# One_Digit_7_Seg_Display.net
KiCad netlist of a schematic drawn in Altium Designer
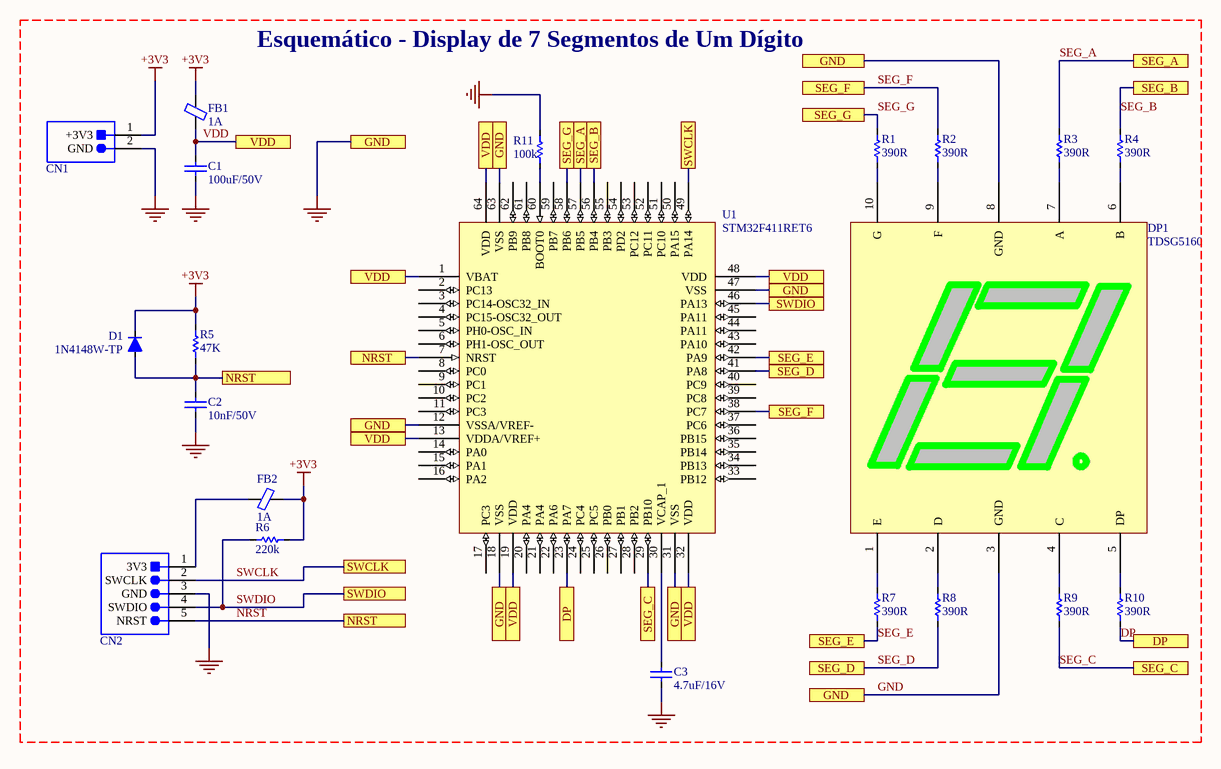
[diagram p0: One_Digit_7_Seg_Display.SchDoc]

(export (version "E")
  (design (tool "Eeschema 10.0.6"))
  (components
    (comp (ref "C1")
      (value "100uF/50V")
      (footprint "Capacitor 0805")
      (description "Cap Ceramic 0.1uF 50V X7R 20% SMD 0805 125C Paper T/R")
      (fields
        (field (name "MANUFACTURER") "Yageo")
        (field (name "MANUFACTURER PART NUMBER") "CC0805MRX7R9BB104")
      )
      (libsource (lib "Roniere_Lib") (part "CC0805MRX7R9BB104"))
    )
    (comp (ref "C2")
      (value "10nF/50V")
      (footprint "Capacitor 0805")
      (description "Cap Cer 0805 10NF 50V C0G 1%")
      (fields
        (field (name "MANUFACTURER") "KEMET")
        (field (name "MANUFACTURER PART NUMBER") "C0805X103F5GEC7210")
      )
      (libsource (lib "Roniere_Lib") (part "C0805X103F5GEC7210"))
    )
    (comp (ref "C3")
      (value "4.7uF/16V")
      (footprint "Capacitor 0805 4.7uF")
      (description "Multilayer Ceramic Capacitors MLCC - SMD/SMT 16volts 4.7uF X5R 20%")
      (fields
        (field (name "MANUFACTURER") "KEMET")
        (field (name "MANUFACTURER PART NUMBER") "C0805C475M4PACTU")
      )
      (libsource (lib "Roniere_Lib") (part "C0805C475M4PACTU"))
    )
    (comp (ref "CN1")
      (value "PCMC2-02 - Alimentação +3V3")
      (footprint "Header Male Horizontal 2X1")
      (libsource (lib "Roniere_Lib") (part "PCMC2-02 - Alimentação +3V3"))
    )
    (comp (ref "CN2")
      (value "PCMC2-05 - Gravacao STM32")
      (footprint "Header Macho Horizontal 5x1 - Gravacao STM32")
      (libsource (lib "Roniere_Lib") (part "PCMC2-05 - Gravacao STM32"))
    )
    (comp (ref "D1")
      (value "1N4148W-TP")
      (footprint "SOD123")
      (description "MICRO COMMERCIAL COMPONENTS - 1N4148W-TP - SWITCHING DIODE, 150mA, 100V, SOD123, FU")
      (fields (field (name "MANUFACTURER") "MCC"))
      (libsource (lib "Roniere_Lib") (part "1N4148W-TP"))
    )
    (comp (ref "DP1")
      (value "TDSG5160")
      (footprint "TDSG5160")
      (description "Displays Module 1DIGIT 8LED Green CC 10-Pin DIP Module")
      (fields
        (field (name "MANUFACTURER") "Vishay Semiconductors")
        (field (name "MANUFACTURER PART NUMBER") "TDSG5160")
      )
      (libsource (lib "Roniere_Lib") (part "TDSG5160"))
    )
    (comp (ref "FB1")
      (value "1A")
      (footprint "Ferrite 0805")
      (description "FERRITE BEAD 0805 1LN")
      (fields
        (field (name "MANUFACTURER") "Fair-Rite")
        (field (name "MANUFACTURER PART NUMBER") "2508051027Y1")
      )
      (libsource (lib "Roniere_Lib") (part "Bead 1A 0805"))
    )
    (comp (ref "FB2")
      (value "1A")
      (footprint "Ferrite 0805")
      (description "FERRITE BEAD 0805 1LN")
      (fields
        (field (name "MANUFACTURER") "Fair-Rite")
        (field (name "MANUFACTURER PART NUMBER") "2508051027Y1")
      )
      (libsource (lib "Roniere_Lib") (part "Bead 1A 0805"))
    )
    (comp (ref "R1")
      (value "390R")
      (footprint "Resistor 0805 390R")
      (fields
        (field (name "MANUFACTURER") "Yageo")
        (field (name "MANUFACTURER PART NUMBER") "RC0805JR-07390RL")
        (field (name "TOLERANCE") "5%")
      )
      (libsource (lib "Roniere_Lib") (part "RC0805JR-07390RL"))
    )
    (comp (ref "R2")
      (value "390R")
      (footprint "Resistor 0805 390R")
      (fields
        (field (name "MANUFACTURER") "Yageo")
        (field (name "MANUFACTURER PART NUMBER") "RC0805JR-07390RL")
        (field (name "TOLERANCE") "5%")
      )
      (libsource (lib "Roniere_Lib") (part "RC0805JR-07390RL"))
    )
    (comp (ref "R3")
      (value "390R")
      (footprint "Resistor 0805 390R")
      (fields
        (field (name "MANUFACTURER") "Yageo")
        (field (name "MANUFACTURER PART NUMBER") "RC0805JR-07390RL")
        (field (name "TOLERANCE") "5%")
      )
      (libsource (lib "Roniere_Lib") (part "RC0805JR-07390RL"))
    )
    (comp (ref "R4")
      (value "390R")
      (footprint "Resistor 0805 390R")
      (fields
        (field (name "MANUFACTURER") "Yageo")
        (field (name "MANUFACTURER PART NUMBER") "RC0805JR-07390RL")
        (field (name "TOLERANCE") "5%")
      )
      (libsource (lib "Roniere_Lib") (part "RC0805JR-07390RL"))
    )
    (comp (ref "R5")
      (value "47K")
      (footprint "Resistor 0805 47k")
      (fields
        (field (name "MANUFACTURER") "Yageo")
        (field (name "MANUFACTURER PART NUMBER") "RC0805JR-0747KL")
        (field (name "TOLERANCE") "5%")
      )
      (libsource (lib "Roniere_Lib") (part "RC0805JR-0747KL"))
    )
    (comp (ref "R6")
      (value "220k")
      (footprint "Resistor 0805 220k")
      (description "YAGEO - RC0805JR-07220KL - RES, 220K, 5%, 0.125W, 0805, THICK FILM")
      (fields
        (field (name "MANUFACTURER") "Yageo")
        (field (name "MANUFACTURER PART NUMBER") "RC0805JR-07220KL")
      )
      (libsource (lib "Roniere_Lib") (part "RC0805JR-07220KL"))
    )
    (comp (ref "R7")
      (value "390R")
      (footprint "Resistor 0805 390R")
      (fields
        (field (name "MANUFACTURER") "Yageo")
        (field (name "MANUFACTURER PART NUMBER") "RC0805JR-07390RL")
        (field (name "TOLERANCE") "5%")
      )
      (libsource (lib "Roniere_Lib") (part "RC0805JR-07390RL"))
    )
    (comp (ref "R8")
      (value "390R")
      (footprint "Resistor 0805 390R")
      (fields
        (field (name "MANUFACTURER") "Yageo")
        (field (name "MANUFACTURER PART NUMBER") "RC0805JR-07390RL")
        (field (name "TOLERANCE") "5%")
      )
      (libsource (lib "Roniere_Lib") (part "RC0805JR-07390RL"))
    )
    (comp (ref "R9")
      (value "390R")
      (footprint "Resistor 0805 390R")
      (fields
        (field (name "MANUFACTURER") "Yageo")
        (field (name "MANUFACTURER PART NUMBER") "RC0805JR-07390RL")
        (field (name "TOLERANCE") "5%")
      )
      (libsource (lib "Roniere_Lib") (part "RC0805JR-07390RL"))
    )
    (comp (ref "R10")
      (value "390R")
      (footprint "Resistor 0805 390R")
      (fields
        (field (name "MANUFACTURER") "Yageo")
        (field (name "MANUFACTURER PART NUMBER") "RC0805JR-07390RL")
        (field (name "TOLERANCE") "5%")
      )
      (libsource (lib "Roniere_Lib") (part "RC0805JR-07390RL"))
    )
    (comp (ref "R11")
      (value "100k")
      (footprint "RESISTOR 0805 100K")
      (description "Res Thick Film 0805 100K Ohm 5% 1/8W 100ppm/C Molded SMD SMD Paper T/R")
      (fields
        (field (name "MANUFACTURER") "Yageo")
        (field (name "MANUFACTURER PART NUMBER") "RC0805JR-07100KL")
      )
      (libsource (lib "Roniere_Lib") (part "RC0805JR-07100KL"))
    )
    (comp (ref "U1")
      (value "STM32F411RET6")
      (footprint "LQFP64")
      (description "IC MCU 32BIT 512KB FLASH 64LQFP")
      (fields
        (field (name "MANUFACTURER") "STMicroelectronics")
        (field (name "MANUFACTURER PART NUMBER") "STM32F411RET6")
      )
      (libsource (lib "Roneire_Lib") (part "STM32F411RET6"))
    )
  )
  (nets
    (net (code "1") (name "+3V3") (class "Default")
      (node (ref "CN1") (pin "1") (pinfunction "+3V3_1") (pintype "passive"))
      (node (ref "D1") (pin "2") (pinfunction "K_2") (pintype "passive"))
      (node (ref "FB1") (pin "2") (pinfunction "2_2") (pintype "passive"))
      (node (ref "FB2") (pin "2") (pinfunction "2_2") (pintype "passive"))
      (node (ref "R5") (pin "2") (pinfunction "2_2") (pintype "passive"))
      (node (ref "R6") (pin "2") (pinfunction "2_2") (pintype "passive"))
    )
    (net (code "2") (name "/DP") (class "Default")
      (node (ref "R10") (pin "1") (pinfunction "1_1") (pintype "passive"))
      (node (ref "U1") (pin "23") (pinfunction "PA7_23") (pintype "bidirectional"))
    )
    (net (code "3") (name "/NRST") (class "Default")
      (node (ref "C2") (pin "2") (pinfunction "2_2") (pintype "passive"))
      (node (ref "CN2") (pin "5") (pinfunction "NRST_5") (pintype "passive"))
      (node (ref "D1") (pin "1") (pinfunction "A_1") (pintype "passive"))
      (node (ref "R5") (pin "1") (pinfunction "1_1") (pintype "passive"))
      (node (ref "U1") (pin "7") (pinfunction "NRST_7") (pintype "input"))
    )
    (net (code "4") (name "/SEG_A") (class "Default")
      (node (ref "R3") (pin "2") (pinfunction "2_2") (pintype "passive"))
      (node (ref "U1") (pin "57") (pinfunction "PB5_57") (pintype "bidirectional"))
    )
    (net (code "5") (name "/SEG_B") (class "Default")
      (node (ref "R4") (pin "2") (pinfunction "2_2") (pintype "passive"))
      (node (ref "U1") (pin "56") (pinfunction "PB4_56") (pintype "bidirectional"))
    )
    (net (code "6") (name "/SEG_C") (class "Default")
      (node (ref "R9") (pin "1") (pinfunction "1_1") (pintype "passive"))
      (node (ref "U1") (pin "29") (pinfunction "PB10_29") (pintype "bidirectional"))
    )
    (net (code "7") (name "/SEG_D") (class "Default")
      (node (ref "R8") (pin "1") (pinfunction "1_1") (pintype "passive"))
      (node (ref "U1") (pin "41") (pinfunction "PA8_41") (pintype "bidirectional"))
    )
    (net (code "8") (name "/SEG_E") (class "Default")
      (node (ref "R7") (pin "1") (pinfunction "1_1") (pintype "passive"))
      (node (ref "U1") (pin "42") (pinfunction "PA9_42") (pintype "bidirectional"))
    )
    (net (code "9") (name "/SEG_F") (class "Default")
      (node (ref "R2") (pin "2") (pinfunction "2_2") (pintype "passive"))
      (node (ref "U1") (pin "38") (pinfunction "PC7_38") (pintype "bidirectional"))
    )
    (net (code "10") (name "/SEG_G") (class "Default")
      (node (ref "R1") (pin "2") (pinfunction "2_2") (pintype "passive"))
      (node (ref "U1") (pin "58") (pinfunction "PB6_58") (pintype "bidirectional"))
    )
    (net (code "11") (name "/SWCLK") (class "Default")
      (node (ref "CN2") (pin "2") (pinfunction "SWCLK_2") (pintype "passive"))
      (node (ref "U1") (pin "49") (pinfunction "PA14_49") (pintype "bidirectional"))
    )
    (net (code "12") (name "/SWDIO") (class "Default")
      (node (ref "CN2") (pin "4") (pinfunction "SWDIO_4") (pintype "passive"))
      (node (ref "R6") (pin "1") (pinfunction "1_1") (pintype "passive"))
      (node (ref "U1") (pin "46") (pinfunction "PA13_46") (pintype "bidirectional"))
    )
    (net (code "13") (name "/VDD") (class "Default")
      (node (ref "C1") (pin "2") (pinfunction "2_2") (pintype "passive"))
      (node (ref "FB1") (pin "1") (pinfunction "1_1") (pintype "passive"))
      (node (ref "U1") (pin "1") (pinfunction "VBAT_1") (pintype "power_in"))
      (node (ref "U1") (pin "13") (pinfunction "VDDA/VREF+_13") (pintype "power_in"))
      (node (ref "U1") (pin "19") (pinfunction "VDD_19") (pintype "power_in"))
      (node (ref "U1") (pin "32") (pinfunction "VDD_32") (pintype "power_in"))
      (node (ref "U1") (pin "48") (pinfunction "VDD_48") (pintype "power_in"))
      (node (ref "U1") (pin "64") (pinfunction "VDD_64") (pintype "power_in"))
    )
    (net (code "14") (name "GND") (class "Default")
      (node (ref "C1") (pin "1") (pinfunction "1_1") (pintype "passive"))
      (node (ref "C2") (pin "1") (pinfunction "1_1") (pintype "passive"))
      (node (ref "C3") (pin "1") (pinfunction "1_1") (pintype "passive"))
      (node (ref "CN1") (pin "2") (pinfunction "GND_2") (pintype "passive"))
      (node (ref "CN2") (pin "3") (pinfunction "GND_3") (pintype "passive"))
      (node (ref "DP1") (pin "3") (pinfunction "GND_3") (pintype "passive"))
      (node (ref "DP1") (pin "8") (pinfunction "GND_8") (pintype "passive"))
      (node (ref "R11") (pin "2") (pinfunction "2_2") (pintype "passive"))
      (node (ref "U1") (pin "12") (pinfunction "VSSA/VREF-_12") (pintype "power_in"))
      (node (ref "U1") (pin "18") (pinfunction "VSS_18") (pintype "power_in"))
      (node (ref "U1") (pin "31") (pinfunction "VSS_31") (pintype "power_in"))
      (node (ref "U1") (pin "47") (pinfunction "VSS_47") (pintype "power_in"))
      (node (ref "U1") (pin "63") (pinfunction "VSS_63") (pintype "power_in"))
    )
    (net (code "15") (name "Net-(CN2-3V3)") (class "Default")
      (node (ref "CN2") (pin "1") (pinfunction "3V3_1") (pintype "passive"))
      (node (ref "FB2") (pin "1") (pinfunction "1_1") (pintype "passive"))
    )
    (net (code "16") (name "Net-(DP1-A)") (class "Default")
      (node (ref "DP1") (pin "7") (pinfunction "A_7") (pintype "passive"))
      (node (ref "R3") (pin "1") (pinfunction "1_1") (pintype "passive"))
    )
    (net (code "17") (name "Net-(DP1-B)") (class "Default")
      (node (ref "DP1") (pin "6") (pinfunction "B_6") (pintype "passive"))
      (node (ref "R4") (pin "1") (pinfunction "1_1") (pintype "passive"))
    )
    (net (code "18") (name "Net-(DP1-C)") (class "Default")
      (node (ref "DP1") (pin "4") (pinfunction "C_4") (pintype "passive"))
      (node (ref "R9") (pin "2") (pinfunction "2_2") (pintype "passive"))
    )
    (net (code "19") (name "Net-(DP1-D)") (class "Default")
      (node (ref "DP1") (pin "2") (pinfunction "D_2") (pintype "passive"))
      (node (ref "R8") (pin "2") (pinfunction "2_2") (pintype "passive"))
    )
    (net (code "20") (name "Net-(DP1-DP)") (class "Default")
      (node (ref "DP1") (pin "5") (pinfunction "DP_5") (pintype "passive"))
      (node (ref "R10") (pin "2") (pinfunction "2_2") (pintype "passive"))
    )
    (net (code "21") (name "Net-(DP1-E)") (class "Default")
      (node (ref "DP1") (pin "1") (pinfunction "E_1") (pintype "passive"))
      (node (ref "R7") (pin "2") (pinfunction "2_2") (pintype "passive"))
    )
    (net (code "22") (name "Net-(DP1-F)") (class "Default")
      (node (ref "DP1") (pin "9") (pinfunction "F_9") (pintype "passive"))
      (node (ref "R2") (pin "1") (pinfunction "1_1") (pintype "passive"))
    )
    (net (code "23") (name "Net-(DP1-G)") (class "Default")
      (node (ref "DP1") (pin "10") (pinfunction "G_10") (pintype "passive"))
      (node (ref "R1") (pin "1") (pinfunction "1_1") (pintype "passive"))
    )
    (net (code "24") (name "Net-(U1-BOOT0)") (class "Default")
      (node (ref "R11") (pin "1") (pinfunction "1_1") (pintype "passive"))
      (node (ref "U1") (pin "60") (pinfunction "BOOT0_60") (pintype "input"))
    )
    (net (code "25") (name "Net-(U1-VCAP_1)") (class "Default")
      (node (ref "C3") (pin "2") (pinfunction "2_2") (pintype "passive"))
      (node (ref "U1") (pin "30") (pinfunction "VCAP_1_30") (pintype "passive"))
    )
    (net (code "26") (name "unconnected-(U1-PA0-Pad14)") (class "Default")
      (node (ref "U1") (pin "14") (pinfunction "PA0_14") (pintype "bidirectional"))
    )
    (net (code "27") (name "unconnected-(U1-PA1-Pad15)") (class "Default")
      (node (ref "U1") (pin "15") (pinfunction "PA1_15") (pintype "bidirectional"))
    )
    (net (code "28") (name "unconnected-(U1-PA2-Pad16)") (class "Default")
      (node (ref "U1") (pin "16") (pinfunction "PA2_16") (pintype "bidirectional"))
    )
    (net (code "29") (name "unconnected-(U1-PA4-Pad20)") (class "Default")
      (node (ref "U1") (pin "20") (pinfunction "PA4_20") (pintype "bidirectional"))
    )
    (net (code "30") (name "unconnected-(U1-PA4-Pad21)") (class "Default")
      (node (ref "U1") (pin "21") (pinfunction "PA4_21") (pintype "bidirectional"))
    )
    (net (code "31") (name "unconnected-(U1-PA6-Pad22)") (class "Default")
      (node (ref "U1") (pin "22") (pinfunction "PA6_22") (pintype "bidirectional"))
    )
    (net (code "32") (name "unconnected-(U1-PA10-Pad43)") (class "Default")
      (node (ref "U1") (pin "43") (pinfunction "PA10_43") (pintype "bidirectional"))
    )
    (net (code "33") (name "unconnected-(U1-PA11-Pad44)") (class "Default")
      (node (ref "U1") (pin "44") (pinfunction "PA11_44") (pintype "bidirectional"))
    )
    (net (code "34") (name "unconnected-(U1-PA11-Pad45)") (class "Default")
      (node (ref "U1") (pin "45") (pinfunction "PA11_45") (pintype "bidirectional"))
    )
    (net (code "35") (name "unconnected-(U1-PA15-Pad50)") (class "Default")
      (node (ref "U1") (pin "50") (pinfunction "PA15_50") (pintype "bidirectional"))
    )
    (net (code "36") (name "unconnected-(U1-PB0-Pad26)") (class "Default")
      (node (ref "U1") (pin "26") (pinfunction "PB0_26") (pintype "bidirectional"))
    )
    (net (code "37") (name "unconnected-(U1-PB1-Pad27)") (class "Default")
      (node (ref "U1") (pin "27") (pinfunction "PB1_27") (pintype "bidirectional"))
    )
    (net (code "38") (name "unconnected-(U1-PB2-Pad28)") (class "Default")
      (node (ref "U1") (pin "28") (pinfunction "PB2_28") (pintype "bidirectional"))
    )
    (net (code "39") (name "unconnected-(U1-PB3-Pad55)") (class "Default")
      (node (ref "U1") (pin "55") (pinfunction "PB3_55") (pintype "bidirectional"))
    )
    (net (code "40") (name "unconnected-(U1-PB7-Pad59)") (class "Default")
      (node (ref "U1") (pin "59") (pinfunction "PB7_59") (pintype "bidirectional"))
    )
    (net (code "41") (name "unconnected-(U1-PB8-Pad61)") (class "Default")
      (node (ref "U1") (pin "61") (pinfunction "PB8_61") (pintype "bidirectional"))
    )
    (net (code "42") (name "unconnected-(U1-PB9-Pad62)") (class "Default")
      (node (ref "U1") (pin "62") (pinfunction "PB9_62") (pintype "bidirectional"))
    )
    (net (code "43") (name "unconnected-(U1-PB12-Pad33)") (class "Default")
      (node (ref "U1") (pin "33") (pinfunction "PB12_33") (pintype "bidirectional"))
    )
    (net (code "44") (name "unconnected-(U1-PB13-Pad34)") (class "Default")
      (node (ref "U1") (pin "34") (pinfunction "PB13_34") (pintype "bidirectional"))
    )
    (net (code "45") (name "unconnected-(U1-PB14-Pad35)") (class "Default")
      (node (ref "U1") (pin "35") (pinfunction "PB14_35") (pintype "bidirectional"))
    )
    (net (code "46") (name "unconnected-(U1-PB15-Pad36)") (class "Default")
      (node (ref "U1") (pin "36") (pinfunction "PB15_36") (pintype "bidirectional"))
    )
    (net (code "47") (name "unconnected-(U1-PC0-Pad8)") (class "Default")
      (node (ref "U1") (pin "8") (pinfunction "PC0_8") (pintype "bidirectional"))
    )
    (net (code "48") (name "unconnected-(U1-PC1-Pad9)") (class "Default")
      (node (ref "U1") (pin "9") (pinfunction "PC1_9") (pintype "bidirectional"))
    )
    (net (code "49") (name "unconnected-(U1-PC2-Pad10)") (class "Default")
      (node (ref "U1") (pin "10") (pinfunction "PC2_10") (pintype "bidirectional"))
    )
    (net (code "50") (name "unconnected-(U1-PC3-Pad11)") (class "Default")
      (node (ref "U1") (pin "11") (pinfunction "PC3_11") (pintype "bidirectional"))
    )
    (net (code "51") (name "unconnected-(U1-PC3-Pad17)") (class "Default")
      (node (ref "U1") (pin "17") (pinfunction "PC3_17") (pintype "bidirectional"))
    )
    (net (code "52") (name "unconnected-(U1-PC4-Pad24)") (class "Default")
      (node (ref "U1") (pin "24") (pinfunction "PC4_24") (pintype "bidirectional"))
    )
    (net (code "53") (name "unconnected-(U1-PC5-Pad25)") (class "Default")
      (node (ref "U1") (pin "25") (pinfunction "PC5_25") (pintype "bidirectional"))
    )
    (net (code "54") (name "unconnected-(U1-PC6-Pad37)") (class "Default")
      (node (ref "U1") (pin "37") (pinfunction "PC6_37") (pintype "bidirectional"))
    )
    (net (code "55") (name "unconnected-(U1-PC8-Pad39)") (class "Default")
      (node (ref "U1") (pin "39") (pinfunction "PC8_39") (pintype "bidirectional"))
    )
    (net (code "56") (name "unconnected-(U1-PC9-Pad40)") (class "Default")
      (node (ref "U1") (pin "40") (pinfunction "PC9_40") (pintype "bidirectional"))
    )
    (net (code "57") (name "unconnected-(U1-PC10-Pad51)") (class "Default")
      (node (ref "U1") (pin "51") (pinfunction "PC10_51") (pintype "bidirectional"))
    )
    (net (code "58") (name "unconnected-(U1-PC11-Pad52)") (class "Default")
      (node (ref "U1") (pin "52") (pinfunction "PC11_52") (pintype "bidirectional"))
    )
    (net (code "59") (name "unconnected-(U1-PC12-Pad53)") (class "Default")
      (node (ref "U1") (pin "53") (pinfunction "PC12_53") (pintype "bidirectional"))
    )
    (net (code "60") (name "unconnected-(U1-PC13-Pad2)") (class "Default")
      (node (ref "U1") (pin "2") (pinfunction "PC13_2") (pintype "bidirectional"))
    )
    (net (code "61") (name "unconnected-(U1-PC14-OSC32_IN-Pad3)") (class "Default")
      (node (ref "U1") (pin "3") (pinfunction "PC14-OSC32_IN_3") (pintype "bidirectional"))
    )
    (net (code "62") (name "unconnected-(U1-PC15-OSC32_OUT-Pad4)") (class "Default")
      (node (ref "U1") (pin "4") (pinfunction "PC15-OSC32_OUT_4") (pintype "bidirectional"))
    )
    (net (code "63") (name "unconnected-(U1-PD2-Pad54)") (class "Default")
      (node (ref "U1") (pin "54") (pinfunction "PD2_54") (pintype "bidirectional"))
    )
    (net (code "64") (name "unconnected-(U1-PH0-OSC_IN-Pad5)") (class "Default")
      (node (ref "U1") (pin "5") (pinfunction "PH0-OSC_IN_5") (pintype "bidirectional"))
    )
    (net (code "65") (name "unconnected-(U1-PH1-OSC_OUT-Pad6)") (class "Default")
      (node (ref "U1") (pin "6") (pinfunction "PH1-OSC_OUT_6") (pintype "bidirectional"))
    )
  )
)
